# MM-H_rev1.net
KiCad netlist of a schematic drawn in EAGLE
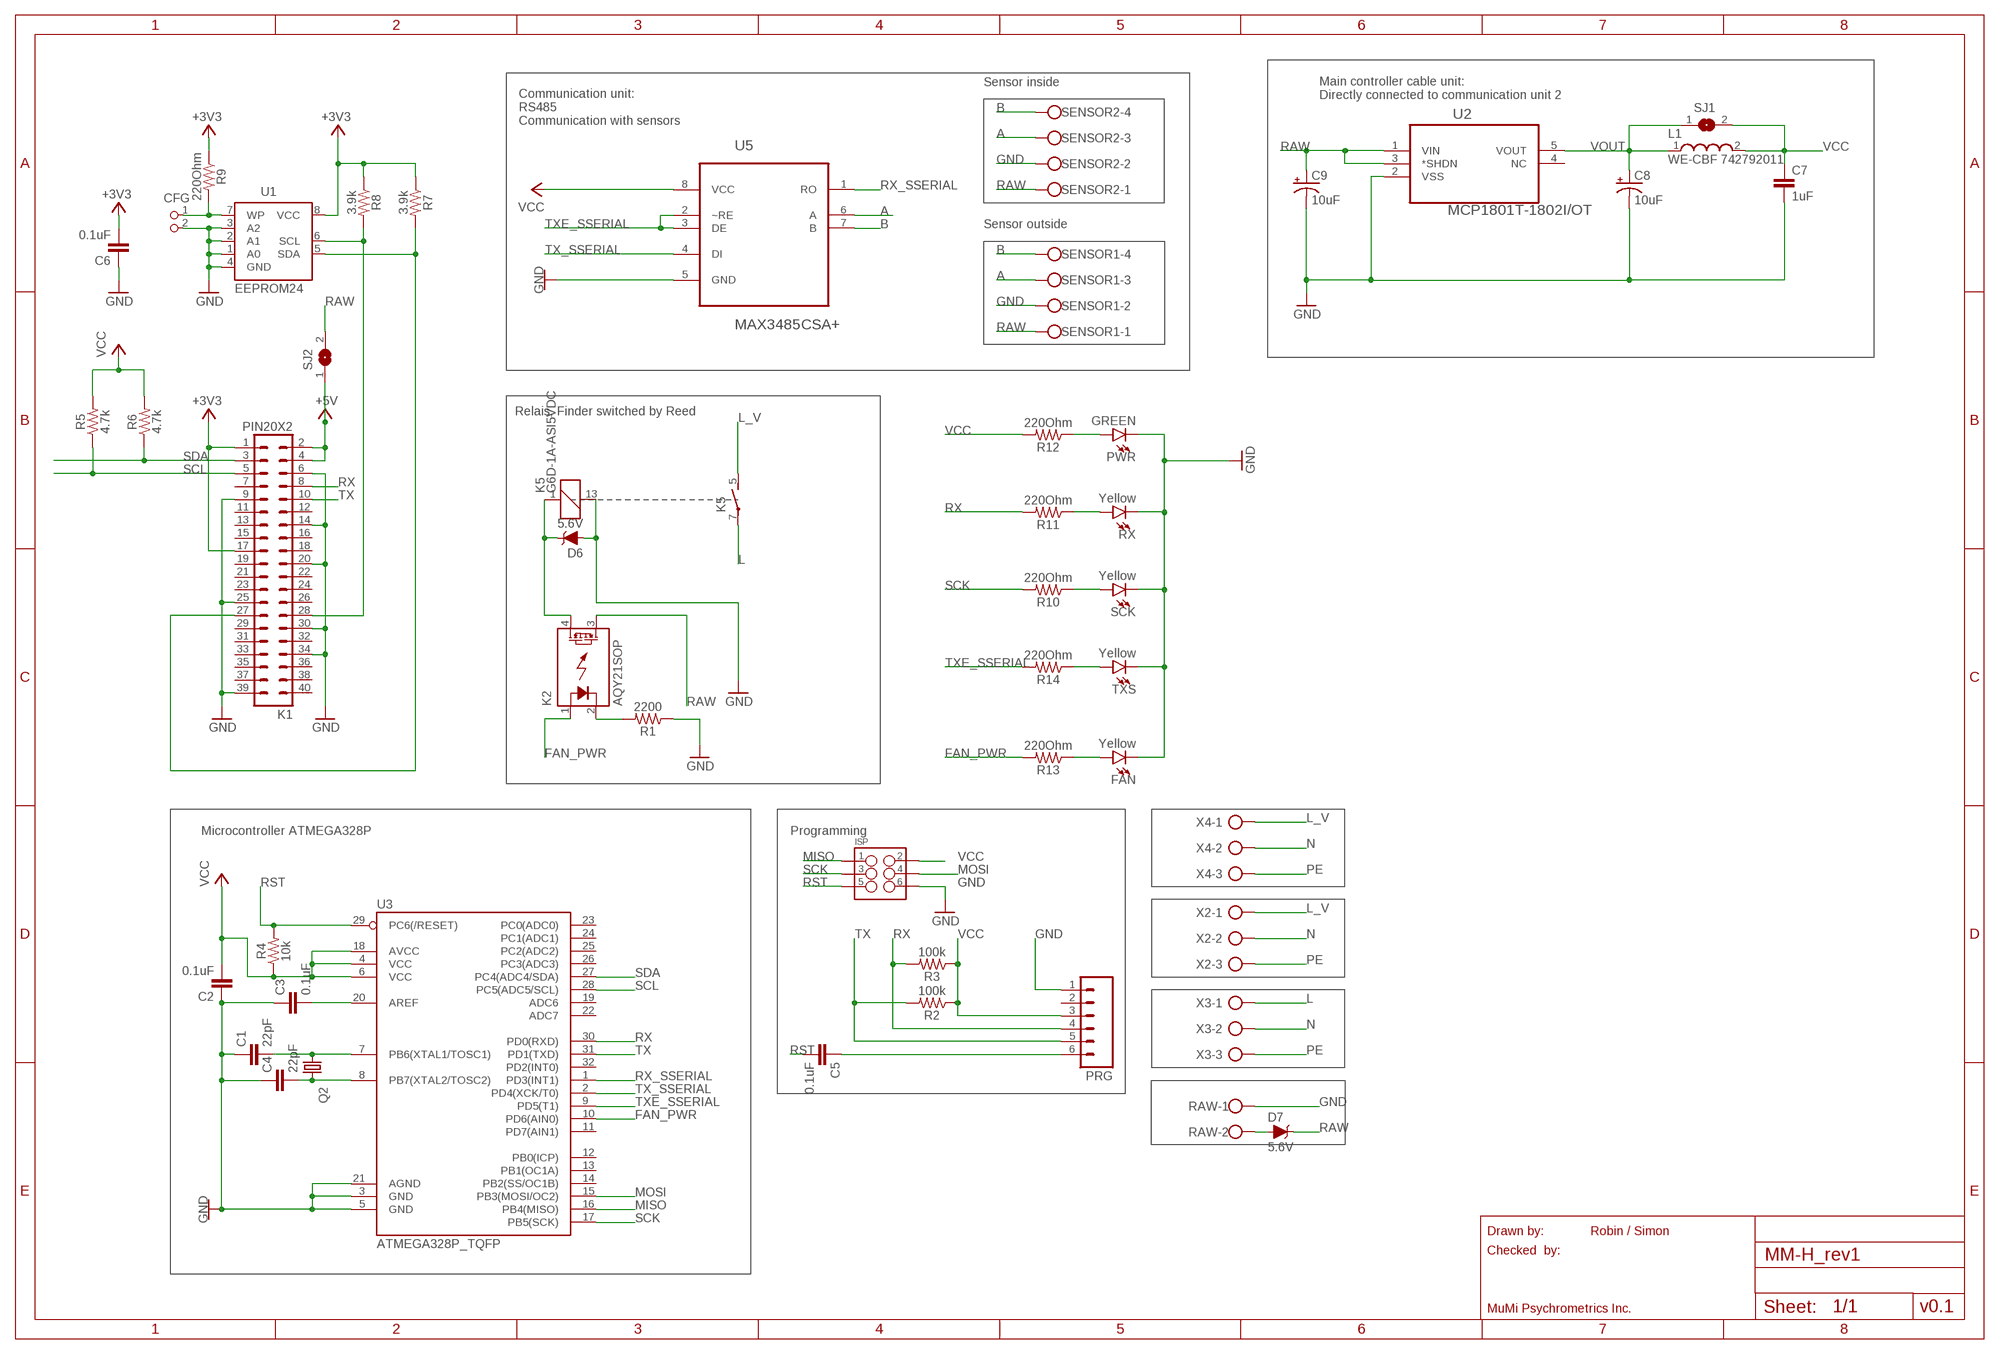
[diagram p0: schematic, sheet 1]

(export (version "E")
  (design (tool "Eeschema 10.0.6"))
  (components
    (comp (ref "C1")
      (value "22pF")
      (footprint "eagle-import:0402")
      (libsource (lib "eagle-import") (part "0.1UF-0402-16V-10%"))
    )
    (comp (ref "C2")
      (value "0.1uF")
      (footprint "eagle-import:0402")
      (libsource (lib "eagle-import") (part "0.1UF-0402-16V-10%"))
    )
    (comp (ref "C3")
      (value "0.1uF")
      (footprint "eagle-import:0402")
      (libsource (lib "eagle-import") (part "0.1UF-0402-16V-10%"))
    )
    (comp (ref "C4")
      (value "22pF")
      (footprint "eagle-import:0402")
      (libsource (lib "eagle-import") (part "0.1UF-0402-16V-10%"))
    )
    (comp (ref "C5")
      (value "0.1uF")
      (footprint "eagle-import:0402")
      (libsource (lib "eagle-import") (part "0.1UF-0402-16V-10%"))
    )
    (comp (ref "C6")
      (value "0.1uF")
      (footprint "eagle-import:0402")
      (libsource (lib "eagle-import") (part "0.1UF-0402-16V-10%"))
    )
    (comp (ref "C7")
      (value "1uF")
      (footprint "eagle-import:0402")
      (libsource (lib "eagle-import") (part "0.1UF-0402-16V-10%"))
    )
    (comp (ref "C8")
      (value "10uF")
      (footprint "eagle-import:EIA3216")
      (libsource (lib "eagle-import") (part "CAP_POL1206"))
    )
    (comp (ref "C9")
      (value "10uF")
      (footprint "eagle-import:EIA3216")
      (libsource (lib "eagle-import") (part "CAP_POL1206"))
    )
    (comp (ref "CFG")
      (value "PIN2_100")
      (footprint "eagle-import:PIN_W_2")
      (libsource (lib "eagle-import") (part "PIN2_100"))
    )
    (comp (ref "D6")
      (value "5.6V")
      (footprint "eagle-import:SOD-323")
      (libsource (lib "eagle-import") (part "DIODE-ZENER-MMSZ5232BS"))
    )
    (comp (ref "D7")
      (value "5.6V")
      (footprint "eagle-import:SOD-323")
      (libsource (lib "eagle-import") (part "DIODE-ZENER-MMSZ5232BS"))
    )
    (comp (ref "FAN")
      (value "Yellow")
      (footprint "eagle-import:LED-0603")
      (libsource (lib "eagle-import") (part "LED-YELLOW0603-SMART"))
    )
    (comp (ref "ISP")
      (value "M03X2POGO_PINS")
      (footprint "eagle-import:2X3_POGO")
      (libsource (lib "eagle-import") (part "M03X2POGO_PINS"))
    )
    (comp (ref "K1")
      (value "PIN20X2")
      (footprint "eagle-import:PIN_20X2")
      (libsource (lib "eagle-import") (part "PIN20X2"))
    )
    (comp (ref "K2")
      (value "AQY21SOP")
      (footprint "eagle-import:SOP04")
      (libsource (lib "eagle-import") (part "AQYSOP21"))
    )
    (comp (ref "K5")
      (value "G6D-1A-ASI5VDC")
      (footprint "eagle-import:G6D")
      (libsource (lib "eagle-import") (part "G6D?-1A-ASI5VDC"))
    )
    (comp (ref "L1")
      (value "WE-CBF 742792011")
      (footprint "eagle-import:WE-CBF_0805(W=3.0)")
      (libsource (lib "eagle-import") (part "WE-CBF_0805(WB/HS)"))
    )
    (comp (ref "PRG")
      (value "M06SILK_FEMALE_PTH")
      (footprint "eagle-import:1X06")
      (libsource (lib "eagle-import") (part "M06SILK_FEMALE_PTH"))
    )
    (comp (ref "PWR")
      (value "GREEN")
      (footprint "eagle-import:LED-0603")
      (libsource (lib "eagle-import") (part "LED-GREEN0603"))
    )
    (comp (ref "Q2")
      (value "KX-K")
      (footprint "eagle-import:11.4X4.5")
      (libsource (lib "eagle-import") (part "KX-K"))
    )
    (comp (ref "R1")
      (value "2200")
      (footprint "eagle-import:0402")
      (libsource (lib "eagle-import") (part "RESISTOR0402"))
    )
    (comp (ref "R2")
      (value "100k")
      (footprint "eagle-import:0402")
      (libsource (lib "eagle-import") (part "RESISTOR0402"))
    )
    (comp (ref "R3")
      (value "100k")
      (footprint "eagle-import:0402")
      (libsource (lib "eagle-import") (part "RESISTOR0402"))
    )
    (comp (ref "R4")
      (value "10k")
      (footprint "eagle-import:0402")
      (libsource (lib "eagle-import") (part "RESISTOR0402"))
    )
    (comp (ref "R5")
      (value "4.7k")
      (footprint "eagle-import:0402")
      (libsource (lib "eagle-import") (part "RESISTOR0402"))
    )
    (comp (ref "R6")
      (value "4.7k")
      (footprint "eagle-import:0402")
      (libsource (lib "eagle-import") (part "RESISTOR0402"))
    )
    (comp (ref "R7")
      (value "3.9k")
      (footprint "eagle-import:0402")
      (libsource (lib "eagle-import") (part "RESISTOR0402"))
    )
    (comp (ref "R8")
      (value "3.9k")
      (footprint "eagle-import:0402")
      (libsource (lib "eagle-import") (part "RESISTOR0402"))
    )
    (comp (ref "R9")
      (value "220Ohm")
      (footprint "eagle-import:0402")
      (libsource (lib "eagle-import") (part "RESISTOR0402"))
    )
    (comp (ref "R10")
      (value "220Ohm")
      (footprint "eagle-import:0402")
      (libsource (lib "eagle-import") (part "RESISTOR0402"))
    )
    (comp (ref "R11")
      (value "220Ohm")
      (footprint "eagle-import:0402")
      (libsource (lib "eagle-import") (part "RESISTOR0402"))
    )
    (comp (ref "R12")
      (value "220Ohm")
      (footprint "eagle-import:0402")
      (libsource (lib "eagle-import") (part "RESISTOR0402"))
    )
    (comp (ref "R13")
      (value "220Ohm")
      (footprint "eagle-import:0402")
      (libsource (lib "eagle-import") (part "RESISTOR0402"))
    )
    (comp (ref "R14")
      (value "220Ohm")
      (footprint "eagle-import:0402")
      (libsource (lib "eagle-import") (part "RESISTOR0402"))
    )
    (comp (ref "RAW")
      (value "W237-102")
      (footprint "eagle-import:W237-102")
      (fields (field (name "MPN") "237-102"))
      (libsource (lib "eagle-import") (part "W237-102"))
    )
    (comp (ref "RX")
      (value "Yellow")
      (footprint "eagle-import:LED-0603")
      (libsource (lib "eagle-import") (part "LED-YELLOW0603-SMART"))
    )
    (comp (ref "SCK")
      (value "Yellow")
      (footprint "eagle-import:LED-0603")
      (libsource (lib "eagle-import") (part "LED-YELLOW0603-SMART"))
    )
    (comp (ref "SENSOR1")
      (value "W237-4")
      (footprint "eagle-import:W237-4")
      (libsource (lib "eagle-import") (part "W237-4"))
    )
    (comp (ref "SENSOR2")
      (value "W237-4")
      (footprint "eagle-import:W237-4")
      (libsource (lib "eagle-import") (part "W237-4"))
    )
    (comp (ref "SJ1") (value "SJ") (footprint "eagle-import:SJ") (libsource (lib "eagle-import") (part "SJ")))
    (comp (ref "SJ2") (value "SJ") (footprint "eagle-import:SJ") (libsource (lib "eagle-import") (part "SJ")))
    (comp (ref "TXS")
      (value "Yellow")
      (footprint "eagle-import:LED-0603")
      (libsource (lib "eagle-import") (part "LED-YELLOW0603-SMART"))
    )
    (comp (ref "U1")
      (value "EEPROM24")
      (footprint "eagle-import:SOIC8")
      (libsource (lib "eagle-import") (part "EEPROM24"))
    )
    (comp (ref "U2")
      (value "MCP1801T-1802I/OT")
      (footprint "eagle-import:SOT95P270X145-5N")
      (libsource (lib "eagle-import") (part "MCP1801T-1802I/OT"))
    )
    (comp (ref "U3")
      (value "ATMEGA328P_TQFP")
      (footprint "eagle-import:TQFP32-08")
      (libsource (lib "eagle-import") (part "ATMEGA328P_TQFP"))
    )
    (comp (ref "U5")
      (value "MAX3485CSA+")
      (footprint "eagle-import:SOIC127P600X175-8N")
      (libsource (lib "eagle-import") (part "MAX3485CSA+"))
    )
    (comp (ref "X2")
      (value "AK500/3")
      (footprint "eagle-import:AK500_3")
      (libsource (lib "eagle-import") (part "AK500/3"))
    )
    (comp (ref "X3")
      (value "AK500/3")
      (footprint "eagle-import:AK500_3")
      (libsource (lib "eagle-import") (part "AK500/3"))
    )
    (comp (ref "X4")
      (value "AK500/3")
      (footprint "eagle-import:AK500_3")
      (libsource (lib "eagle-import") (part "AK500/3"))
    )
  )
  (nets
    (net (code "1") (name "+3V3") (class "Default")
      (node (ref "C6") (pin "2") (pinfunction "2_2") (pintype "passive"))
      (node (ref "K1") (pin "1") (pinfunction "1_1") (pintype "passive"))
      (node (ref "K1") (pin "17") (pinfunction "17_17") (pintype "passive"))
      (node (ref "R7") (pin "1") (pinfunction "1_1") (pintype "passive"))
      (node (ref "R8") (pin "1") (pinfunction "1_1") (pintype "passive"))
      (node (ref "R9") (pin "1") (pinfunction "1_1") (pintype "passive"))
      (node (ref "U1") (pin "8") (pinfunction "VCC_8") (pintype "power_in"))
    )
    (net (code "2") (name "+5V") (class "Default")
      (node (ref "K1") (pin "2") (pinfunction "2_2") (pintype "passive"))
      (node (ref "K1") (pin "4") (pinfunction "4_4") (pintype "passive"))
      (node (ref "SJ2") (pin "1") (pinfunction "1_1") (pintype "passive"))
    )
    (net (code "3") (name "/A") (class "Default")
      (node (ref "SENSOR1") (pin "3") (pinfunction "KL_3") (pintype "passive"))
      (node (ref "SENSOR2") (pin "3") (pinfunction "KL_3") (pintype "passive"))
      (node (ref "U5") (pin "6") (pinfunction "A_6") (pintype "bidirectional"))
    )
    (net (code "4") (name "/B") (class "Default")
      (node (ref "SENSOR1") (pin "4") (pinfunction "KL_4") (pintype "passive"))
      (node (ref "SENSOR2") (pin "4") (pinfunction "KL_4") (pintype "passive"))
      (node (ref "U5") (pin "7") (pinfunction "B_7") (pintype "bidirectional"))
    )
    (net (code "5") (name "/FAN_PWR") (class "Default")
      (node (ref "K2") (pin "1") (pinfunction "A_1") (pintype "passive"))
      (node (ref "R13") (pin "2") (pinfunction "2_2") (pintype "passive"))
      (node (ref "U3") (pin "10") (pinfunction "PD6(AIN0)_10") (pintype "bidirectional"))
    )
    (net (code "6") (name "/L") (class "Default")
      (node (ref "K5") (pin "7") (pinfunction "P_7") (pintype "passive"))
      (node (ref "X3") (pin "1") (pinfunction "KL_1") (pintype "passive"))
    )
    (net (code "7") (name "/L_V") (class "Default")
      (node (ref "K5") (pin "5") (pinfunction "S_5") (pintype "passive"))
      (node (ref "X2") (pin "1") (pinfunction "KL_1") (pintype "passive"))
      (node (ref "X4") (pin "1") (pinfunction "KL_1") (pintype "passive"))
    )
    (net (code "8") (name "/MISO") (class "Default")
      (node (ref "ISP") (pin "P$1") (pinfunction "1_P$1") (pintype "bidirectional"))
      (node (ref "U3") (pin "16") (pinfunction "PB4(MISO)_16") (pintype "bidirectional"))
    )
    (net (code "9") (name "/MOSI") (class "Default")
      (node (ref "ISP") (pin "P$4") (pinfunction "4_P$4") (pintype "bidirectional"))
      (node (ref "U3") (pin "15") (pinfunction "PB3(MOSI/OC2)_15") (pintype "bidirectional"))
    )
    (net (code "10") (name "/N") (class "Default")
      (node (ref "X2") (pin "2") (pinfunction "KL_2") (pintype "passive"))
      (node (ref "X3") (pin "2") (pinfunction "KL_2") (pintype "passive"))
      (node (ref "X4") (pin "2") (pinfunction "KL_2") (pintype "passive"))
    )
    (net (code "11") (name "/PE") (class "Default")
      (node (ref "X2") (pin "3") (pinfunction "KL_3") (pintype "passive"))
      (node (ref "X3") (pin "3") (pinfunction "KL_3") (pintype "passive"))
      (node (ref "X4") (pin "3") (pinfunction "KL_3") (pintype "passive"))
    )
    (net (code "12") (name "/RAW") (class "Default")
      (node (ref "C9") (pin "A") (pinfunction "+_A") (pintype "passive"))
      (node (ref "D7") (pin "C") (pinfunction "C_C") (pintype "passive"))
      (node (ref "K2") (pin "3") (pinfunction "DS2_3") (pintype "passive"))
      (node (ref "SENSOR1") (pin "1") (pinfunction "KL_1") (pintype "passive"))
      (node (ref "SENSOR2") (pin "1") (pinfunction "KL_1") (pintype "passive"))
      (node (ref "SJ2") (pin "2") (pinfunction "2_2") (pintype "passive"))
      (node (ref "U2") (pin "1") (pinfunction "VIN_1") (pintype "input"))
      (node (ref "U2") (pin "3") (pinfunction "*SHDN_3") (pintype "input"))
    )
    (net (code "13") (name "/RST") (class "Default")
      (node (ref "C5") (pin "2") (pinfunction "2_2") (pintype "passive"))
      (node (ref "ISP") (pin "P$5") (pinfunction "5_P$5") (pintype "bidirectional"))
      (node (ref "R4") (pin "2") (pinfunction "2_2") (pintype "passive"))
      (node (ref "U3") (pin "29") (pinfunction "PC6(/RESET)_29") (pintype "bidirectional"))
    )
    (net (code "14") (name "/RX") (class "Default")
      (node (ref "K1") (pin "8") (pinfunction "8_8") (pintype "passive"))
      (node (ref "PRG") (pin "4") (pinfunction "4_4") (pintype "passive"))
      (node (ref "R11") (pin "2") (pinfunction "2_2") (pintype "passive"))
      (node (ref "R3") (pin "2") (pinfunction "2_2") (pintype "passive"))
      (node (ref "U3") (pin "30") (pinfunction "PD0(RXD)_30") (pintype "bidirectional"))
    )
    (net (code "15") (name "/RX_SSERIAL") (class "Default")
      (node (ref "U3") (pin "1") (pinfunction "PD3(INT1)_1") (pintype "bidirectional"))
      (node (ref "U5") (pin "1") (pinfunction "RO_1") (pintype "output"))
    )
    (net (code "16") (name "/SCK") (class "Default")
      (node (ref "ISP") (pin "P$3") (pinfunction "3_P$3") (pintype "bidirectional"))
      (node (ref "R10") (pin "2") (pinfunction "2_2") (pintype "passive"))
      (node (ref "U3") (pin "17") (pinfunction "PB5(SCK)_17") (pintype "bidirectional"))
    )
    (net (code "17") (name "/SCL") (class "Default")
      (node (ref "K1") (pin "5") (pinfunction "5_5") (pintype "passive"))
      (node (ref "R5") (pin "1") (pinfunction "1_1") (pintype "passive"))
      (node (ref "U3") (pin "28") (pinfunction "PC5(ADC5/SCL)_28") (pintype "bidirectional"))
    )
    (net (code "18") (name "/SDA") (class "Default")
      (node (ref "K1") (pin "3") (pinfunction "3_3") (pintype "passive"))
      (node (ref "R6") (pin "1") (pinfunction "1_1") (pintype "passive"))
      (node (ref "U3") (pin "27") (pinfunction "PC4(ADC4/SDA)_27") (pintype "bidirectional"))
    )
    (net (code "19") (name "/TX") (class "Default")
      (node (ref "K1") (pin "10") (pinfunction "10_10") (pintype "passive"))
      (node (ref "PRG") (pin "5") (pinfunction "5_5") (pintype "passive"))
      (node (ref "R2") (pin "2") (pinfunction "2_2") (pintype "passive"))
      (node (ref "U3") (pin "31") (pinfunction "PD1(TXD)_31") (pintype "bidirectional"))
    )
    (net (code "20") (name "/TXE_SSERIAL") (class "Default")
      (node (ref "R14") (pin "2") (pinfunction "2_2") (pintype "passive"))
      (node (ref "U3") (pin "9") (pinfunction "PD5(T1)_9") (pintype "bidirectional"))
      (node (ref "U5") (pin "2") (pinfunction "~{RE}_2") (pintype "input"))
      (node (ref "U5") (pin "3") (pinfunction "DE_3") (pintype "input"))
    )
    (net (code "21") (name "/TX_SSERIAL") (class "Default")
      (node (ref "U3") (pin "2") (pinfunction "PD4(XCK/T0)_2") (pintype "bidirectional"))
      (node (ref "U5") (pin "4") (pinfunction "DI_4") (pintype "input"))
    )
    (net (code "22") (name "/VOUT") (class "Default")
      (node (ref "C8") (pin "A") (pinfunction "+_A") (pintype "passive"))
      (node (ref "L1") (pin "1") (pinfunction "1_1") (pintype "passive"))
      (node (ref "SJ1") (pin "1") (pinfunction "1_1") (pintype "passive"))
      (node (ref "U2") (pin "5") (pinfunction "VOUT_5") (pintype "output"))
    )
    (net (code "23") (name "GND") (class "Default")
      (node (ref "C1") (pin "1") (pinfunction "1_1") (pintype "passive"))
      (node (ref "C2") (pin "1") (pinfunction "1_1") (pintype "passive"))
      (node (ref "C3") (pin "1") (pinfunction "1_1") (pintype "passive"))
      (node (ref "C4") (pin "1") (pinfunction "1_1") (pintype "passive"))
      (node (ref "C6") (pin "1") (pinfunction "1_1") (pintype "passive"))
      (node (ref "C7") (pin "2") (pinfunction "2_2") (pintype "passive"))
      (node (ref "C8") (pin "C") (pinfunction "-_C") (pintype "passive"))
      (node (ref "C9") (pin "C") (pinfunction "-_C") (pintype "passive"))
      (node (ref "CFG") (pin "2") (pinfunction "2_2") (pintype "passive"))
      (node (ref "D6") (pin "A") (pinfunction "A_A") (pintype "passive"))
      (node (ref "FAN") (pin "C") (pinfunction "C_C") (pintype "passive"))
      (node (ref "ISP") (pin "P$6") (pinfunction "6_P$6") (pintype "bidirectional"))
      (node (ref "K1") (pin "14") (pinfunction "14_14") (pintype "passive"))
      (node (ref "K1") (pin "20") (pinfunction "20_20") (pintype "passive"))
      (node (ref "K1") (pin "25") (pinfunction "25_25") (pintype "passive"))
      (node (ref "K1") (pin "30") (pinfunction "30_30") (pintype "passive"))
      (node (ref "K1") (pin "34") (pinfunction "34_34") (pintype "passive"))
      (node (ref "K1") (pin "39") (pinfunction "39_39") (pintype "passive"))
      (node (ref "K1") (pin "6") (pinfunction "6_6") (pintype "passive"))
      (node (ref "K1") (pin "9") (pinfunction "9_9") (pintype "passive"))
      (node (ref "K5") (pin "13") (pinfunction "2_13") (pintype "passive"))
      (node (ref "PRG") (pin "1") (pinfunction "1_1") (pintype "passive"))
      (node (ref "PWR") (pin "C") (pinfunction "C_C") (pintype "passive"))
      (node (ref "R1") (pin "1") (pinfunction "1_1") (pintype "passive"))
      (node (ref "RAW") (pin "1") (pinfunction "KL_1") (pintype "passive"))
      (node (ref "RX") (pin "C") (pinfunction "C_C") (pintype "passive"))
      (node (ref "SCK") (pin "C") (pinfunction "C_C") (pintype "passive"))
      (node (ref "SENSOR1") (pin "2") (pinfunction "KL_2") (pintype "passive"))
      (node (ref "SENSOR2") (pin "2") (pinfunction "KL_2") (pintype "passive"))
      (node (ref "TXS") (pin "C") (pinfunction "C_C") (pintype "passive"))
      (node (ref "U1") (pin "1") (pinfunction "A0_1") (pintype "input"))
      (node (ref "U1") (pin "2") (pinfunction "A1_2") (pintype "input"))
      (node (ref "U1") (pin "3") (pinfunction "A2_3") (pintype "input"))
      (node (ref "U1") (pin "4") (pinfunction "GND_4") (pintype "power_in"))
      (node (ref "U2") (pin "2") (pinfunction "VSS_2") (pintype "passive"))
      (node (ref "U3") (pin "21") (pinfunction "AGND_21") (pintype "bidirectional"))
      (node (ref "U3") (pin "3") (pinfunction "GND_3") (pintype "bidirectional"))
      (node (ref "U3") (pin "5") (pinfunction "GND_5") (pintype "bidirectional"))
      (node (ref "U5") (pin "5") (pinfunction "GND_5") (pintype "passive"))
    )
    (net (code "24") (name "Net-(C5-Pad1)") (class "Default")
      (node (ref "C5") (pin "1") (pinfunction "1_1") (pintype "passive"))
      (node (ref "PRG") (pin "6") (pinfunction "6_6") (pintype "passive"))
    )
    (net (code "25") (name "Net-(FAN-PadA)") (class "Default")
      (node (ref "FAN") (pin "A") (pinfunction "A_A") (pintype "passive"))
      (node (ref "R13") (pin "1") (pinfunction "1_1") (pintype "passive"))
    )
    (net (code "26") (name "Net-(K2-DS1)") (class "Default")
      (node (ref "D6") (pin "C") (pinfunction "C_C") (pintype "passive"))
      (node (ref "K2") (pin "4") (pinfunction "DS1_4") (pintype "passive"))
      (node (ref "K5") (pin "1") (pinfunction "1_1") (pintype "passive"))
    )
    (net (code "27") (name "Net-(K2-K)") (class "Default")
      (node (ref "K2") (pin "2") (pinfunction "K_2") (pintype "passive"))
      (node (ref "R1") (pin "2") (pinfunction "2_2") (pintype "passive"))
    )
    (net (code "28") (name "Net-(PWR-PadA)") (class "Default")
      (node (ref "PWR") (pin "A") (pinfunction "A_A") (pintype "passive"))
      (node (ref "R12") (pin "1") (pinfunction "1_1") (pintype "passive"))
    )
    (net (code "29") (name "Net-(R10-Pad1)") (class "Default")
      (node (ref "R10") (pin "1") (pinfunction "1_1") (pintype "passive"))
      (node (ref "SCK") (pin "A") (pinfunction "A_A") (pintype "passive"))
    )
    (net (code "30") (name "Net-(R11-Pad1)") (class "Default")
      (node (ref "R11") (pin "1") (pinfunction "1_1") (pintype "passive"))
      (node (ref "RX") (pin "A") (pinfunction "A_A") (pintype "passive"))
    )
    (net (code "31") (name "Net-(R14-Pad1)") (class "Default")
      (node (ref "R14") (pin "1") (pinfunction "1_1") (pintype "passive"))
      (node (ref "TXS") (pin "A") (pinfunction "A_A") (pintype "passive"))
    )
    (net (code "32") (name "Net-(RAWB-KL)") (class "Default")
      (node (ref "D7") (pin "A") (pinfunction "A_A") (pintype "passive"))
      (node (ref "RAW") (pin "2") (pinfunction "KL_2") (pintype "passive"))
    )
    (net (code "33") (name "Net-(U1-SCL)") (class "Default")
      (node (ref "K1") (pin "28") (pinfunction "28_28") (pintype "passive"))
      (node (ref "R8") (pin "2") (pinfunction "2_2") (pintype "passive"))
      (node (ref "U1") (pin "6") (pinfunction "SCL_6") (pintype "input"))
    )
    (net (code "34") (name "Net-(U1-SDA)") (class "Default")
      (node (ref "K1") (pin "27") (pinfunction "27_27") (pintype "passive"))
      (node (ref "R7") (pin "2") (pinfunction "2_2") (pintype "passive"))
      (node (ref "U1") (pin "5") (pinfunction "SDA_5") (pintype "bidirectional"))
    )
    (net (code "35") (name "Net-(U1-WP)") (class "Default")
      (node (ref "CFG") (pin "1") (pinfunction "1_1") (pintype "passive"))
      (node (ref "R9") (pin "2") (pinfunction "2_2") (pintype "passive"))
      (node (ref "U1") (pin "7") (pinfunction "WP_7") (pintype "input"))
    )
    (net (code "36") (name "Net-(U3-AREF)") (class "Default")
      (node (ref "C3") (pin "2") (pinfunction "2_2") (pintype "passive"))
      (node (ref "U3") (pin "20") (pinfunction "AREF_20") (pintype "bidirectional"))
    )
    (net (code "37") (name "Net-(U3-PB6(XTAL1{slash}TOSC1))") (class "Default")
      (node (ref "C1") (pin "2") (pinfunction "2_2") (pintype "passive"))
      (node (ref "Q2") (pin "1") (pinfunction "1_1") (pintype "passive"))
      (node (ref "U3") (pin "7") (pinfunction "PB6(XTAL1/TOSC1)_7") (pintype "bidirectional"))
    )
    (net (code "38") (name "Net-(U3-PB7(XTAL2{slash}TOSC2))") (class "Default")
      (node (ref "C4") (pin "2") (pinfunction "2_2") (pintype "passive"))
      (node (ref "Q2") (pin "2") (pinfunction "2_2") (pintype "passive"))
      (node (ref "U3") (pin "8") (pinfunction "PB7(XTAL2/TOSC2)_8") (pintype "bidirectional"))
    )
    (net (code "39") (name "VCC") (class "Default")
      (node (ref "C2") (pin "2") (pinfunction "2_2") (pintype "passive"))
      (node (ref "C7") (pin "1") (pinfunction "1_1") (pintype "passive"))
      (node (ref "ISP") (pin "P$2") (pinfunction "2_P$2") (pintype "bidirectional"))
      (node (ref "L1") (pin "2") (pinfunction "2_2") (pintype "passive"))
      (node (ref "PRG") (pin "3") (pinfunction "3_3") (pintype "passive"))
      (node (ref "R12") (pin "2") (pinfunction "2_2") (pintype "passive"))
      (node (ref "R2") (pin "1") (pinfunction "1_1") (pintype "passive"))
      (node (ref "R3") (pin "1") (pinfunction "1_1") (pintype "passive"))
      (node (ref "R4") (pin "1") (pinfunction "1_1") (pintype "passive"))
      (node (ref "R5") (pin "2") (pinfunction "2_2") (pintype "passive"))
      (node (ref "R6") (pin "2") (pinfunction "2_2") (pintype "passive"))
      (node (ref "SJ1") (pin "2") (pinfunction "2_2") (pintype "passive"))
      (node (ref "U3") (pin "18") (pinfunction "AVCC_18") (pintype "bidirectional"))
      (node (ref "U3") (pin "4") (pinfunction "VCC_4") (pintype "bidirectional"))
      (node (ref "U3") (pin "6") (pinfunction "VCC_6") (pintype "bidirectional"))
      (node (ref "U5") (pin "8") (pinfunction "VCC_8") (pintype "power_in"))
    )
    (net (code "40") (name "unconnected-(K1-Pad7)") (class "Default")
      (node (ref "K1") (pin "7") (pinfunction "7_7") (pintype "passive"))
    )
    (net (code "41") (name "unconnected-(K1-Pad11)") (class "Default")
      (node (ref "K1") (pin "11") (pinfunction "11_11") (pintype "passive"))
    )
    (net (code "42") (name "unconnected-(K1-Pad12)") (class "Default")
      (node (ref "K1") (pin "12") (pinfunction "12_12") (pintype "passive"))
    )
    (net (code "43") (name "unconnected-(K1-Pad13)") (class "Default")
      (node (ref "K1") (pin "13") (pinfunction "13_13") (pintype "passive"))
    )
    (net (code "44") (name "unconnected-(K1-Pad15)") (class "Default")
      (node (ref "K1") (pin "15") (pinfunction "15_15") (pintype "passive"))
    )
    (net (code "45") (name "unconnected-(K1-Pad16)") (class "Default")
      (node (ref "K1") (pin "16") (pinfunction "16_16") (pintype "passive"))
    )
    (net (code "46") (name "unconnected-(K1-Pad18)") (class "Default")
      (node (ref "K1") (pin "18") (pinfunction "18_18") (pintype "passive"))
    )
    (net (code "47") (name "unconnected-(K1-Pad19)") (class "Default")
      (node (ref "K1") (pin "19") (pinfunction "19_19") (pintype "passive"))
    )
    (net (code "48") (name "unconnected-(K1-Pad21)") (class "Default")
      (node (ref "K1") (pin "21") (pinfunction "21_21") (pintype "passive"))
    )
    (net (code "49") (name "unconnected-(K1-Pad22)") (class "Default")
      (node (ref "K1") (pin "22") (pinfunction "22_22") (pintype "passive"))
    )
    (net (code "50") (name "unconnected-(K1-Pad23)") (class "Default")
      (node (ref "K1") (pin "23") (pinfunction "23_23") (pintype "passive"))
    )
    (net (code "51") (name "unconnected-(K1-Pad24)") (class "Default")
      (node (ref "K1") (pin "24") (pinfunction "24_24") (pintype "passive"))
    )
    (net (code "52") (name "unconnected-(K1-Pad26)") (class "Default")
      (node (ref "K1") (pin "26") (pinfunction "26_26") (pintype "passive"))
    )
    (net (code "53") (name "unconnected-(K1-Pad29)") (class "Default")
      (node (ref "K1") (pin "29") (pinfunction "29_29") (pintype "passive"))
    )
    (net (code "54") (name "unconnected-(K1-Pad31)") (class "Default")
      (node (ref "K1") (pin "31") (pinfunction "31_31") (pintype "passive"))
    )
    (net (code "55") (name "unconnected-(K1-Pad32)") (class "Default")
      (node (ref "K1") (pin "32") (pinfunction "32_32") (pintype "passive"))
    )
    (net (code "56") (name "unconnected-(K1-Pad33)") (class "Default")
      (node (ref "K1") (pin "33") (pinfunction "33_33") (pintype "passive"))
    )
    (net (code "57") (name "unconnected-(K1-Pad35)") (class "Default")
      (node (ref "K1") (pin "35") (pinfunction "35_35") (pintype "passive"))
    )
    (net (code "58") (name "unconnected-(K1-Pad36)") (class "Default")
      (node (ref "K1") (pin "36") (pinfunction "36_36") (pintype "passive"))
    )
    (net (code "59") (name "unconnected-(K1-Pad37)") (class "Default")
      (node (ref "K1") (pin "37") (pinfunction "37_37") (pintype "passive"))
    )
    (net (code "60") (name "unconnected-(K1-Pad38)") (class "Default")
      (node (ref "K1") (pin "38") (pinfunction "38_38") (pintype "passive"))
    )
    (net (code "61") (name "unconnected-(K1-Pad40)") (class "Default")
      (node (ref "K1") (pin "40") (pinfunction "40_40") (pintype "passive"))
    )
    (net (code "62") (name "unconnected-(PRG-Pad2)") (class "Default")
      (node (ref "PRG") (pin "2") (pinfunction "2_2") (pintype "passive"))
    )
    (net (code "63") (name "unconnected-(U2-NC-Pad4)") (class "Default")
      (node (ref "U2") (pin "4") (pinfunction "NC_4") (pintype "no_connect"))
    )
    (net (code "64") (name "unconnected-(U3-ADC6-Pad19)") (class "Default")
      (node (ref "U3") (pin "19") (pinfunction "ADC6_19") (pintype "bidirectional"))
    )
    (net (code "65") (name "unconnected-(U3-ADC7-Pad22)") (class "Default")
      (node (ref "U3") (pin "22") (pinfunction "ADC7_22") (pintype "bidirectional"))
    )
    (net (code "66") (name "unconnected-(U3-PB0(ICP)-Pad12)") (class "Default")
      (node (ref "U3") (pin "12") (pinfunction "PB0(ICP)_12") (pintype "bidirectional"))
    )
    (net (code "67") (name "unconnected-(U3-PB1(OC1A)-Pad13)") (class "Default")
      (node (ref "U3") (pin "13") (pinfunction "PB1(OC1A)_13") (pintype "bidirectional"))
    )
    (net (code "68") (name "unconnected-(U3-PB2(SS{slash}OC1B)-Pad14)") (class "Default")
      (node (ref "U3") (pin "14") (pinfunction "PB2(SS/OC1B)_14") (pintype "bidirectional"))
    )
    (net (code "69") (name "unconnected-(U3-PC0(ADC0)-Pad23)") (class "Default")
      (node (ref "U3") (pin "23") (pinfunction "PC0(ADC0)_23") (pintype "bidirectional"))
    )
    (net (code "70") (name "unconnected-(U3-PC1(ADC1)-Pad24)") (class "Default")
      (node (ref "U3") (pin "24") (pinfunction "PC1(ADC1)_24") (pintype "bidirectional"))
    )
    (net (code "71") (name "unconnected-(U3-PC2(ADC2)-Pad25)") (class "Default")
      (node (ref "U3") (pin "25") (pinfunction "PC2(ADC2)_25") (pintype "bidirectional"))
    )
    (net (code "72") (name "unconnected-(U3-PC3(ADC3)-Pad26)") (class "Default")
      (node (ref "U3") (pin "26") (pinfunction "PC3(ADC3)_26") (pintype "bidirectional"))
    )
    (net (code "73") (name "unconnected-(U3-PD2(INT0)-Pad32)") (class "Default")
      (node (ref "U3") (pin "32") (pinfunction "PD2(INT0)_32") (pintype "bidirectional"))
    )
    (net (code "74") (name "unconnected-(U3-PD7(AIN1)-Pad11)") (class "Default")
      (node (ref "U3") (pin "11") (pinfunction "PD7(AIN1)_11") (pintype "bidirectional"))
    )
  )
)
